# jtag-adapter-3-1.net
KiCad netlist of a schematic drawn in EAGLE
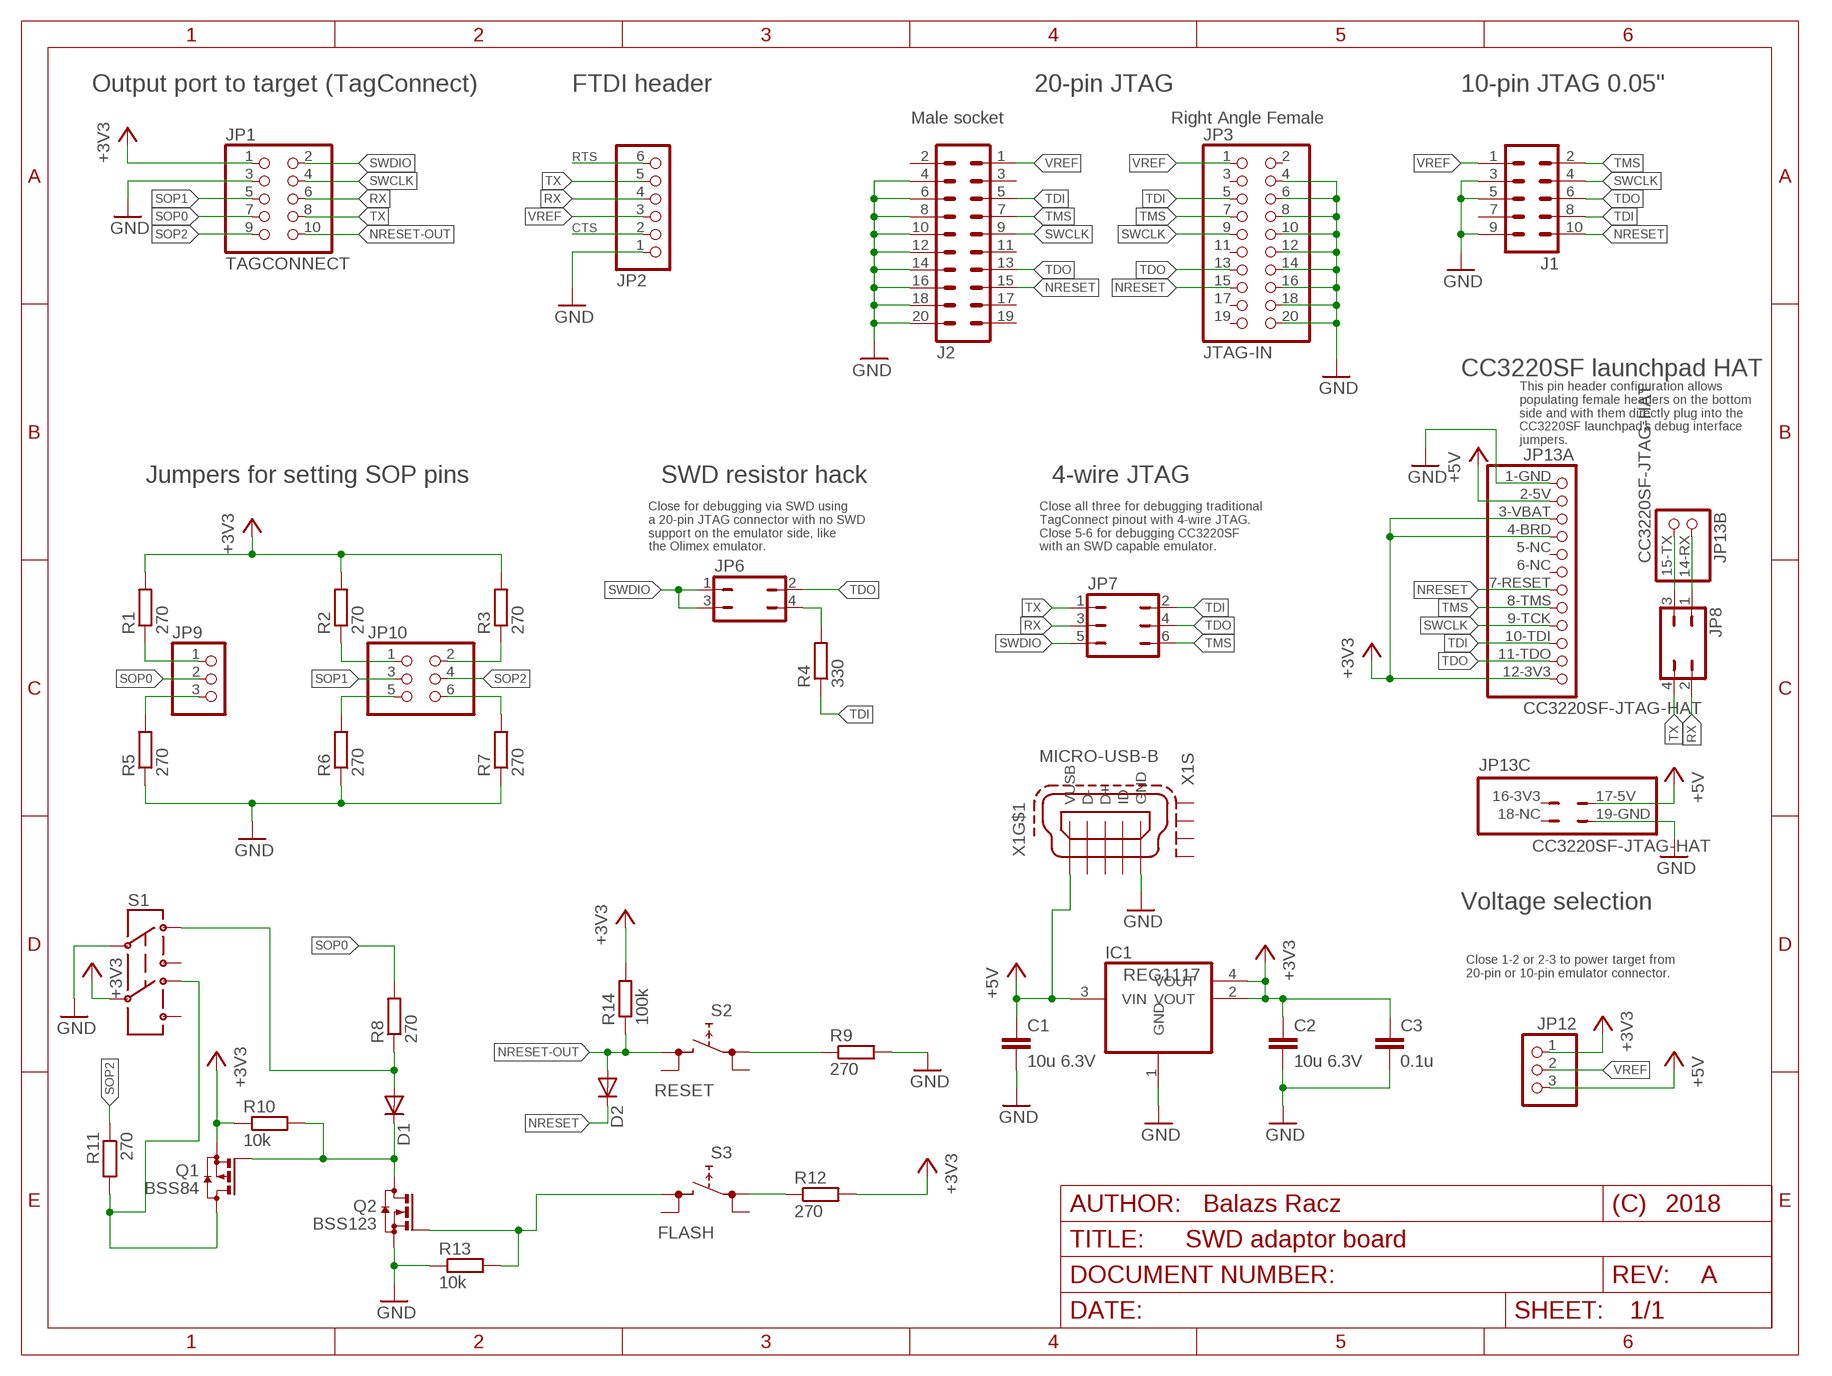
[diagram p0: schematic, sheet 1]

(export (version "E")
  (design (tool "Eeschema 10.0.6"))
  (components
    (comp (ref "C1")
      (value "10u 6.3V")
      (footprint "eagle-import:C0603K")
      (libsource (lib "eagle-import") (part "C-EUC0603K"))
    )
    (comp (ref "C2")
      (value "10u 6.3V")
      (footprint "eagle-import:C0603K")
      (libsource (lib "eagle-import") (part "C-EUC0603K"))
    )
    (comp (ref "C3")
      (value "0.1u")
      (footprint "eagle-import:C0603K")
      (libsource (lib "eagle-import") (part "C-EUC0603K"))
    )
    (comp (ref "D1")
      (value "DIODE-MINIMELF")
      (footprint "eagle-import:MINIMELF")
      (libsource (lib "eagle-import") (part "DIODE-MINIMELF"))
    )
    (comp (ref "D2")
      (value "DIODE-MINIMELF")
      (footprint "eagle-import:MINIMELF")
      (libsource (lib "eagle-import") (part "DIODE-MINIMELF"))
    )
    (comp (ref "IC1")
      (value "REG1117")
      (footprint "eagle-import:SOT223")
      (libsource (lib "eagle-import") (part "REG1117"))
    )
    (comp (ref "J1")
      (value "MA05-2_0.05X0.05")
      (footprint "eagle-import:MA05-2_0.05_X_0.05")
      (libsource (lib "eagle-import") (part "MA05-2_0.05X0.05"))
    )
    (comp (ref "J2")
      (value "MA10-2S")
      (footprint "eagle-import:MA10-2-SHROUDED")
      (libsource (lib "eagle-import") (part "MA10-2S"))
    )
    (comp (ref "JP1")
      (value "TAGCONNECT")
      (footprint "eagle-import:CON10M")
      (libsource (lib "eagle-import") (part "PINHD-2X5CN"))
    )
    (comp (ref "JP2")
      (value "PINHD-1X6")
      (footprint "eagle-import:1X06")
      (libsource (lib "eagle-import") (part "PINHD-1X6"))
    )
    (comp (ref "JP3")
      (value "JTAG-IN")
      (footprint "eagle-import:2X10")
      (libsource (lib "eagle-import") (part "PINHD-2X10"))
    )
    (comp (ref "JP6")
      (value "JP2Q")
      (footprint "eagle-import:JP2Q")
      (libsource (lib "eagle-import") (part "JP2Q"))
    )
    (comp (ref "JP7")
      (value "JP3Q")
      (footprint "eagle-import:JP3Q")
      (libsource (lib "eagle-import") (part "JP3Q"))
    )
    (comp (ref "JP8")
      (value "JP2Q")
      (footprint "eagle-import:JP2Q")
      (libsource (lib "eagle-import") (part "JP2Q"))
    )
    (comp (ref "JP9")
      (value "PINHD-1X3")
      (footprint "eagle-import:1X03")
      (libsource (lib "eagle-import") (part "PINHD-1X3"))
    )
    (comp (ref "JP10")
      (value "PINHD-2X3")
      (footprint "eagle-import:2X03")
      (libsource (lib "eagle-import") (part "PINHD-2X3"))
    )
    (comp (ref "JP12")
      (value "PINHD-1X3")
      (footprint "eagle-import:1X03")
      (libsource (lib "eagle-import") (part "PINHD-1X3"))
    )
    (comp (ref "JP13")
      (value "CC3220SF-JTAG-HAT")
      (footprint "eagle-import:JTAG-LAUNCHPAD-3220SF")
      (libsource (lib "eagle-import") (part "CC3220SF-JTAG-HAT"))
    )
    (comp (ref "Q1")
      (value "BSS84")
      (footprint "eagle-import:SOT23")
      (libsource (lib "eagle-import") (part "BSS84"))
    )
    (comp (ref "Q2")
      (value "BSS123")
      (footprint "eagle-import:SOT23")
      (libsource (lib "eagle-import") (part "BSS123"))
    )
    (comp (ref "R1")
      (value "270")
      (footprint "eagle-import:R0805")
      (libsource (lib "eagle-import") (part "R-EU_R0805"))
    )
    (comp (ref "R2")
      (value "270")
      (footprint "eagle-import:R0805")
      (libsource (lib "eagle-import") (part "R-EU_R0805"))
    )
    (comp (ref "R3")
      (value "270")
      (footprint "eagle-import:R0805")
      (libsource (lib "eagle-import") (part "R-EU_R0805"))
    )
    (comp (ref "R4")
      (value "330")
      (footprint "eagle-import:R0805")
      (libsource (lib "eagle-import") (part "R-EU_R0805"))
    )
    (comp (ref "R5")
      (value "270")
      (footprint "eagle-import:R0805")
      (libsource (lib "eagle-import") (part "R-EU_R0805"))
    )
    (comp (ref "R6")
      (value "270")
      (footprint "eagle-import:R0805")
      (libsource (lib "eagle-import") (part "R-EU_R0805"))
    )
    (comp (ref "R7")
      (value "270")
      (footprint "eagle-import:R0805")
      (libsource (lib "eagle-import") (part "R-EU_R0805"))
    )
    (comp (ref "R8")
      (value "270")
      (footprint "eagle-import:R0805")
      (libsource (lib "eagle-import") (part "R-EU_R0805"))
    )
    (comp (ref "R9")
      (value "270")
      (footprint "eagle-import:R0805")
      (libsource (lib "eagle-import") (part "R-EU_R0805"))
    )
    (comp (ref "R10")
      (value "10k")
      (footprint "eagle-import:R0805")
      (libsource (lib "eagle-import") (part "R-EU_R0805"))
    )
    (comp (ref "R11")
      (value "270")
      (footprint "eagle-import:R0805")
      (libsource (lib "eagle-import") (part "R-EU_R0805"))
    )
    (comp (ref "R12")
      (value "270")
      (footprint "eagle-import:R0805")
      (libsource (lib "eagle-import") (part "R-EU_R0805"))
    )
    (comp (ref "R13")
      (value "10k")
      (footprint "eagle-import:R0805")
      (libsource (lib "eagle-import") (part "R-EU_R0805"))
    )
    (comp (ref "R14")
      (value "100k")
      (footprint "eagle-import:R0805")
      (libsource (lib "eagle-import") (part "R-EU_R0805"))
    )
    (comp (ref "S1")
      (value "SWITCH-DPDTJS202011CQN")
      (footprint "eagle-import:DPDT-2.5X3.2MM")
      (libsource (lib "eagle-import") (part "SWITCH-DPDTJS202011CQN"))
    )
    (comp (ref "S2")
      (value "RESET")
      (footprint "eagle-import:TACTSW-6X6")
      (libsource (lib "eagle-import") (part "TACTSW-6X6S"))
    )
    (comp (ref "S3")
      (value "FLASH")
      (footprint "eagle-import:TACTSW-6X6")
      (libsource (lib "eagle-import") (part "TACTSW-6X6S"))
    )
    (comp (ref "X1")
      (value "MICRO-USB-B")
      (footprint "eagle-import:MICRO-B-PAC")
      (libsource (lib "eagle-import") (part "MICRO-USB-B"))
    )
  )
  (nets
    (net (code "1") (name "+3V3") (class "Default")
      (node (ref "C2") (pin "1") (pinfunction "1_1") (pintype "passive"))
      (node (ref "C3") (pin "1") (pinfunction "1_1") (pintype "passive"))
      (node (ref "IC1") (pin "2") (pinfunction "VOUT_2") (pintype "output"))
      (node (ref "IC1") (pin "4") (pinfunction "VOUT_4") (pintype "output"))
      (node (ref "JP1") (pin "1") (pinfunction "1_1") (pintype "passive"))
      (node (ref "JP12") (pin "1") (pinfunction "1_1") (pintype "passive"))
      (node (ref "JP13") (pin "12-3V3") (pinfunction "12_12-3V3") (pintype "passive"))
      (node (ref "JP13") (pin "3-VBAT") (pinfunction "3_3-VBAT") (pintype "passive"))
      (node (ref "JP13") (pin "4-BRD") (pinfunction "4_4-BRD") (pintype "passive"))
      (node (ref "Q1") (pin "2") (pinfunction "S_2") (pintype "passive"))
      (node (ref "R1") (pin "2") (pinfunction "2_2") (pintype "passive"))
      (node (ref "R10") (pin "1") (pinfunction "1_1") (pintype "passive"))
      (node (ref "R12") (pin "2") (pinfunction "2_2") (pintype "passive"))
      (node (ref "R14") (pin "2") (pinfunction "2_2") (pintype "passive"))
      (node (ref "R2") (pin "2") (pinfunction "2_2") (pintype "passive"))
      (node (ref "R3") (pin "2") (pinfunction "2_2") (pintype "passive"))
      (node (ref "S1") (pin "5") (pinfunction "2C_5") (pintype "bidirectional"))
    )
    (net (code "2") (name "+5V") (class "Default")
      (node (ref "C1") (pin "1") (pinfunction "1_1") (pintype "passive"))
      (node (ref "IC1") (pin "3") (pinfunction "VIN_3") (pintype "input"))
      (node (ref "JP12") (pin "3") (pinfunction "3_3") (pintype "passive"))
      (node (ref "JP13") (pin "17-5V") (pinfunction "2_17-5V") (pintype "passive"))
      (node (ref "JP13") (pin "2-5V") (pinfunction "2_2-5V") (pintype "passive"))
      (node (ref "X1") (pin "1") (pinfunction "VUSB_1") (pintype "passive"))
    )
    (net (code "3") (name "/CTS") (class "Default")
      (node (ref "JP2") (pin "2") (pinfunction "2_2") (pintype "passive"))
    )
    (net (code "4") (name "/RTS") (class "Default")
      (node (ref "JP2") (pin "6") (pinfunction "6_6") (pintype "passive"))
    )
    (net (code "5") (name "GND") (class "Default")
      (node (ref "C1") (pin "2") (pinfunction "2_2") (pintype "passive"))
      (node (ref "C2") (pin "2") (pinfunction "2_2") (pintype "passive"))
      (node (ref "C3") (pin "2") (pinfunction "2_2") (pintype "passive"))
      (node (ref "IC1") (pin "1") (pinfunction "GND_1") (pintype "power_in"))
      (node (ref "J1") (pin "3") (pinfunction "3_3") (pintype "passive"))
      (node (ref "J1") (pin "5") (pinfunction "5_5") (pintype "passive"))
      (node (ref "J1") (pin "9") (pinfunction "9_9") (pintype "passive"))
      (node (ref "J2") (pin "10") (pinfunction "10_10") (pintype "passive"))
      (node (ref "J2") (pin "12") (pinfunction "12_12") (pintype "passive"))
      (node (ref "J2") (pin "14") (pinfunction "14_14") (pintype "passive"))
      (node (ref "J2") (pin "16") (pinfunction "16_16") (pintype "passive"))
      (node (ref "J2") (pin "18") (pinfunction "18_18") (pintype "passive"))
      (node (ref "J2") (pin "20") (pinfunction "20_20") (pintype "passive"))
      (node (ref "J2") (pin "4") (pinfunction "4_4") (pintype "passive"))
      (node (ref "J2") (pin "6") (pinfunction "6_6") (pintype "passive"))
      (node (ref "J2") (pin "8") (pinfunction "8_8") (pintype "passive"))
      (node (ref "JP1") (pin "3") (pinfunction "3_3") (pintype "passive"))
      (node (ref "JP13") (pin "1-GND") (pinfunction "1_1-GND") (pintype "passive"))
      (node (ref "JP13") (pin "19-GND") (pinfunction "4_19-GND") (pintype "passive"))
      (node (ref "JP2") (pin "1") (pinfunction "1_1") (pintype "passive"))
      (node (ref "JP3") (pin "10") (pinfunction "10_10") (pintype "passive"))
      (node (ref "JP3") (pin "12") (pinfunction "12_12") (pintype "passive"))
      (node (ref "JP3") (pin "14") (pinfunction "14_14") (pintype "passive"))
      (node (ref "JP3") (pin "16") (pinfunction "16_16") (pintype "passive"))
      (node (ref "JP3") (pin "18") (pinfunction "18_18") (pintype "passive"))
      (node (ref "JP3") (pin "20") (pinfunction "20_20") (pintype "passive"))
      (node (ref "JP3") (pin "4") (pinfunction "4_4") (pintype "passive"))
      (node (ref "JP3") (pin "6") (pinfunction "6_6") (pintype "passive"))
      (node (ref "JP3") (pin "8") (pinfunction "8_8") (pintype "passive"))
      (node (ref "Q2") (pin "2") (pinfunction "S_2") (pintype "passive"))
      (node (ref "R13") (pin "1") (pinfunction "1_1") (pintype "passive"))
      (node (ref "R5") (pin "1") (pinfunction "1_1") (pintype "passive"))
      (node (ref "R6") (pin "1") (pinfunction "1_1") (pintype "passive"))
      (node (ref "R7") (pin "1") (pinfunction "1_1") (pintype "passive"))
      (node (ref "R9") (pin "2") (pinfunction "2_2") (pintype "passive"))
      (node (ref "S1") (pin "2") (pinfunction "1C_2") (pintype "bidirectional"))
      (node (ref "X1") (pin "5") (pinfunction "GND_5") (pintype "passive"))
    )
    (net (code "6") (name "NRESET") (class "Default")
      (node (ref "D2") (pin "C") (pinfunction "C_C") (pintype "passive"))
      (node (ref "J1") (pin "10") (pinfunction "10_10") (pintype "passive"))
      (node (ref "J2") (pin "15") (pinfunction "15_15") (pintype "passive"))
      (node (ref "JP13") (pin "7-RESET") (pinfunction "7_7-RESET") (pintype "passive"))
      (node (ref "JP3") (pin "15") (pinfunction "15_15") (pintype "passive"))
    )
    (net (code "7") (name "NRESET-OUT") (class "Default")
      (node (ref "D2") (pin "A") (pinfunction "A_A") (pintype "passive"))
      (node (ref "JP1") (pin "10") (pinfunction "10_10") (pintype "passive"))
      (node (ref "R14") (pin "1") (pinfunction "1_1") (pintype "passive"))
      (node (ref "S2") (pin "3") (pinfunction "2.1_3") (pintype "passive"))
    )
    (net (code "8") (name "Net-(JP6-Pad4)") (class "Default")
      (node (ref "JP6") (pin "4") (pinfunction "4_4") (pintype "passive"))
      (node (ref "R4") (pin "2") (pinfunction "2_2") (pintype "passive"))
    )
    (net (code "9") (name "Net-(JP9-Pad1)") (class "Default")
      (node (ref "JP9") (pin "1") (pinfunction "1_1") (pintype "passive"))
      (node (ref "R1") (pin "1") (pinfunction "1_1") (pintype "passive"))
    )
    (net (code "10") (name "Net-(JP9-Pad3)") (class "Default")
      (node (ref "JP9") (pin "3") (pinfunction "3_3") (pintype "passive"))
      (node (ref "R5") (pin "2") (pinfunction "2_2") (pintype "passive"))
    )
    (net (code "11") (name "Net-(JP10-Pad1)") (class "Default")
      (node (ref "JP10") (pin "1") (pinfunction "1_1") (pintype "passive"))
      (node (ref "R2") (pin "1") (pinfunction "1_1") (pintype "passive"))
    )
    (net (code "12") (name "Net-(JP10-Pad2)") (class "Default")
      (node (ref "JP10") (pin "2") (pinfunction "2_2") (pintype "passive"))
      (node (ref "R3") (pin "1") (pinfunction "1_1") (pintype "passive"))
    )
    (net (code "13") (name "Net-(JP10-Pad5)") (class "Default")
      (node (ref "JP10") (pin "5") (pinfunction "5_5") (pintype "passive"))
      (node (ref "R6") (pin "2") (pinfunction "2_2") (pintype "passive"))
    )
    (net (code "14") (name "Net-(JP10-Pad6)") (class "Default")
      (node (ref "JP10") (pin "6") (pinfunction "6_6") (pintype "passive"))
      (node (ref "R7") (pin "2") (pinfunction "2_2") (pintype "passive"))
    )
    (net (code "15") (name "Net-(JP13B-1)") (class "Default")
      (node (ref "JP13") (pin "14-RX") (pinfunction "1_14-RX") (pintype "passive"))
      (node (ref "JP8") (pin "1") (pinfunction "1_1") (pintype "passive"))
    )
    (net (code "16") (name "Net-(JP13B-2)") (class "Default")
      (node (ref "JP13") (pin "15-TX") (pinfunction "2_15-TX") (pintype "passive"))
      (node (ref "JP8") (pin "3") (pinfunction "3_3") (pintype "passive"))
    )
    (net (code "17") (name "Net-(Q1-D)") (class "Default")
      (node (ref "Q1") (pin "3") (pinfunction "D_3") (pintype "passive"))
      (node (ref "R11") (pin "2") (pinfunction "2_2") (pintype "passive"))
      (node (ref "S1") (pin "4") (pinfunction "2A_4") (pintype "bidirectional"))
    )
    (net (code "18") (name "Net-(Q1-G)") (class "Default")
      (node (ref "D1") (pin "C") (pinfunction "C_C") (pintype "passive"))
      (node (ref "Q1") (pin "1") (pinfunction "G_1") (pintype "passive"))
      (node (ref "Q2") (pin "3") (pinfunction "D_3") (pintype "passive"))
      (node (ref "R10") (pin "2") (pinfunction "2_2") (pintype "passive"))
    )
    (net (code "19") (name "Net-(Q2-G)") (class "Default")
      (node (ref "Q2") (pin "1") (pinfunction "G_1") (pintype "passive"))
      (node (ref "R13") (pin "2") (pinfunction "2_2") (pintype "passive"))
      (node (ref "S3") (pin "3") (pinfunction "2.1_3") (pintype "passive"))
    )
    (net (code "20") (name "Net-(S1-1A)") (class "Default")
      (node (ref "D1") (pin "A") (pinfunction "A_A") (pintype "passive"))
      (node (ref "R8") (pin "1") (pinfunction "1_1") (pintype "passive"))
      (node (ref "S1") (pin "1") (pinfunction "1A_1") (pintype "bidirectional"))
    )
    (net (code "21") (name "Net-(S2-1.1)") (class "Default")
      (node (ref "R9") (pin "1") (pinfunction "1_1") (pintype "passive"))
      (node (ref "S2") (pin "1") (pinfunction "1.1_1") (pintype "passive"))
    )
    (net (code "22") (name "Net-(S3-1.1)") (class "Default")
      (node (ref "R12") (pin "1") (pinfunction "1_1") (pintype "passive"))
      (node (ref "S3") (pin "1") (pinfunction "1.1_1") (pintype "passive"))
    )
    (net (code "23") (name "RX") (class "Default")
      (node (ref "JP1") (pin "6") (pinfunction "6_6") (pintype "passive"))
      (node (ref "JP2") (pin "4") (pinfunction "4_4") (pintype "passive"))
      (node (ref "JP7") (pin "3") (pinfunction "3_3") (pintype "passive"))
      (node (ref "JP8") (pin "2") (pinfunction "2_2") (pintype "passive"))
    )
    (net (code "24") (name "SOP0") (class "Default")
      (node (ref "JP1") (pin "7") (pinfunction "7_7") (pintype "passive"))
      (node (ref "JP9") (pin "2") (pinfunction "2_2") (pintype "passive"))
      (node (ref "R8") (pin "2") (pinfunction "2_2") (pintype "passive"))
    )
    (net (code "25") (name "SOP1") (class "Default")
      (node (ref "JP1") (pin "5") (pinfunction "5_5") (pintype "passive"))
      (node (ref "JP10") (pin "3") (pinfunction "3_3") (pintype "passive"))
    )
    (net (code "26") (name "SOP2") (class "Default")
      (node (ref "JP1") (pin "9") (pinfunction "9_9") (pintype "passive"))
      (node (ref "JP10") (pin "4") (pinfunction "4_4") (pintype "passive"))
      (node (ref "R11") (pin "1") (pinfunction "1_1") (pintype "passive"))
    )
    (net (code "27") (name "SWCLK") (class "Default")
      (node (ref "J1") (pin "4") (pinfunction "4_4") (pintype "passive"))
      (node (ref "J2") (pin "9") (pinfunction "9_9") (pintype "passive"))
      (node (ref "JP1") (pin "4") (pinfunction "4_4") (pintype "passive"))
      (node (ref "JP13") (pin "9-TCK") (pinfunction "9_9-TCK") (pintype "passive"))
      (node (ref "JP3") (pin "9") (pinfunction "9_9") (pintype "passive"))
    )
    (net (code "28") (name "SWDIO") (class "Default")
      (node (ref "JP1") (pin "2") (pinfunction "2_2") (pintype "passive"))
      (node (ref "JP6") (pin "1") (pinfunction "1_1") (pintype "passive"))
      (node (ref "JP6") (pin "3") (pinfunction "3_3") (pintype "passive"))
      (node (ref "JP7") (pin "5") (pinfunction "5_5") (pintype "passive"))
    )
    (net (code "29") (name "TDI") (class "Default")
      (node (ref "J1") (pin "8") (pinfunction "8_8") (pintype "passive"))
      (node (ref "J2") (pin "5") (pinfunction "5_5") (pintype "passive"))
      (node (ref "JP13") (pin "10-TDI") (pinfunction "10_10-TDI") (pintype "passive"))
      (node (ref "JP3") (pin "5") (pinfunction "5_5") (pintype "passive"))
      (node (ref "JP7") (pin "2") (pinfunction "2_2") (pintype "passive"))
      (node (ref "R4") (pin "1") (pinfunction "1_1") (pintype "passive"))
    )
    (net (code "30") (name "TDO") (class "Default")
      (node (ref "J1") (pin "6") (pinfunction "6_6") (pintype "passive"))
      (node (ref "J2") (pin "13") (pinfunction "13_13") (pintype "passive"))
      (node (ref "JP13") (pin "11-TDO") (pinfunction "11_11-TDO") (pintype "passive"))
      (node (ref "JP3") (pin "13") (pinfunction "13_13") (pintype "passive"))
      (node (ref "JP6") (pin "2") (pinfunction "2_2") (pintype "passive"))
      (node (ref "JP7") (pin "4") (pinfunction "4_4") (pintype "passive"))
    )
    (net (code "31") (name "TMS") (class "Default")
      (node (ref "J1") (pin "2") (pinfunction "2_2") (pintype "passive"))
      (node (ref "J2") (pin "7") (pinfunction "7_7") (pintype "passive"))
      (node (ref "JP13") (pin "8-TMS") (pinfunction "8_8-TMS") (pintype "passive"))
      (node (ref "JP3") (pin "7") (pinfunction "7_7") (pintype "passive"))
      (node (ref "JP7") (pin "6") (pinfunction "6_6") (pintype "passive"))
    )
    (net (code "32") (name "TX") (class "Default")
      (node (ref "JP1") (pin "8") (pinfunction "8_8") (pintype "passive"))
      (node (ref "JP2") (pin "5") (pinfunction "5_5") (pintype "passive"))
      (node (ref "JP7") (pin "1") (pinfunction "1_1") (pintype "passive"))
      (node (ref "JP8") (pin "4") (pinfunction "4_4") (pintype "passive"))
    )
    (net (code "33") (name "VREF") (class "Default")
      (node (ref "J1") (pin "1") (pinfunction "1_1") (pintype "passive"))
      (node (ref "J2") (pin "1") (pinfunction "1_1") (pintype "passive"))
      (node (ref "JP12") (pin "2") (pinfunction "2_2") (pintype "passive"))
      (node (ref "JP2") (pin "3") (pinfunction "3_3") (pintype "passive"))
      (node (ref "JP3") (pin "1") (pinfunction "1_1") (pintype "passive"))
    )
    (net (code "34") (name "unconnected-(J1-Pad7)") (class "Default")
      (node (ref "J1") (pin "7") (pinfunction "7_7") (pintype "passive"))
    )
    (net (code "35") (name "unconnected-(J2-Pad2)") (class "Default")
      (node (ref "J2") (pin "2") (pinfunction "2_2") (pintype "passive"))
    )
    (net (code "36") (name "unconnected-(J2-Pad3)") (class "Default")
      (node (ref "J2") (pin "3") (pinfunction "3_3") (pintype "passive"))
    )
    (net (code "37") (name "unconnected-(J2-Pad11)") (class "Default")
      (node (ref "J2") (pin "11") (pinfunction "11_11") (pintype "passive"))
    )
    (net (code "38") (name "unconnected-(J2-Pad17)") (class "Default")
      (node (ref "J2") (pin "17") (pinfunction "17_17") (pintype "passive"))
    )
    (net (code "39") (name "unconnected-(J2-Pad19)") (class "Default")
      (node (ref "J2") (pin "19") (pinfunction "19_19") (pintype "passive"))
    )
    (net (code "40") (name "unconnected-(JP3-Pad2)") (class "Default")
      (node (ref "JP3") (pin "2") (pinfunction "2_2") (pintype "passive"))
    )
    (net (code "41") (name "unconnected-(JP3-Pad3)") (class "Default")
      (node (ref "JP3") (pin "3") (pinfunction "3_3") (pintype "passive"))
    )
    (net (code "42") (name "unconnected-(JP3-Pad11)") (class "Default")
      (node (ref "JP3") (pin "11") (pinfunction "11_11") (pintype "passive"))
    )
    (net (code "43") (name "unconnected-(JP3-Pad17)") (class "Default")
      (node (ref "JP3") (pin "17") (pinfunction "17_17") (pintype "passive"))
    )
    (net (code "44") (name "unconnected-(JP3-Pad19)") (class "Default")
      (node (ref "JP3") (pin "19") (pinfunction "19_19") (pintype "passive"))
    )
    (net (code "45") (name "unconnected-(JP13A-5-Pad5-NC)") (class "Default")
      (node (ref "JP13") (pin "5-NC") (pinfunction "5_5-NC") (pintype "passive"))
    )
    (net (code "46") (name "unconnected-(JP13A-6-Pad6-NC)") (class "Default")
      (node (ref "JP13") (pin "6-NC") (pinfunction "6_6-NC") (pintype "passive"))
    )
    (net (code "47") (name "unconnected-(JP13C-1-Pad16-3V3)") (class "Default")
      (node (ref "JP13") (pin "16-3V3") (pinfunction "1_16-3V3") (pintype "passive"))
    )
    (net (code "48") (name "unconnected-(JP13C-3-Pad18-NC)") (class "Default")
      (node (ref "JP13") (pin "18-NC") (pinfunction "3_18-NC") (pintype "passive"))
    )
    (net (code "49") (name "unconnected-(S1-1B-Pad3)") (class "Default")
      (node (ref "S1") (pin "3") (pinfunction "1B_3") (pintype "bidirectional"))
    )
    (net (code "50") (name "unconnected-(S1-2B-Pad6)") (class "Default")
      (node (ref "S1") (pin "6") (pinfunction "2B_6") (pintype "bidirectional"))
    )
    (net (code "51") (name "unconnected-(S2-1.2-Pad2)") (class "Default")
      (node (ref "S2") (pin "2") (pinfunction "1.2_2") (pintype "passive"))
    )
    (net (code "52") (name "unconnected-(S2-2.2-Pad4)") (class "Default")
      (node (ref "S2") (pin "4") (pinfunction "2.2_4") (pintype "passive"))
    )
    (net (code "53") (name "unconnected-(S3-1.2-Pad2)") (class "Default")
      (node (ref "S3") (pin "2") (pinfunction "1.2_2") (pintype "passive"))
    )
    (net (code "54") (name "unconnected-(S3-2.2-Pad4)") (class "Default")
      (node (ref "S3") (pin "4") (pinfunction "2.2_4") (pintype "passive"))
    )
    (net (code "55") (name "unconnected-(X1A-D+-Pad3)") (class "Default")
      (node (ref "X1") (pin "3") (pinfunction "D+_3") (pintype "passive"))
    )
    (net (code "56") (name "unconnected-(X1A-D--Pad2)") (class "Default")
      (node (ref "X1") (pin "2") (pinfunction "D-_2") (pintype "passive"))
    )
    (net (code "57") (name "unconnected-(X1A-ID-Pad4)") (class "Default")
      (node (ref "X1") (pin "4") (pinfunction "ID_4") (pintype "passive"))
    )
    (net (code "58") (name "unconnected-(X1B-S1-PadM1)") (class "Default")
      (node (ref "X1") (pin "M1") (pinfunction "S1_M1") (pintype "passive"))
    )
    (net (code "59") (name "unconnected-(X1B-S2-PadM2)") (class "Default")
      (node (ref "X1") (pin "M2") (pinfunction "S2_M2") (pintype "passive"))
    )
    (net (code "60") (name "unconnected-(X1B-S3-PadM3)") (class "Default")
      (node (ref "X1") (pin "M3") (pinfunction "S3_M3") (pintype "passive"))
    )
    (net (code "61") (name "unconnected-(X1B-S4-PadM4)") (class "Default")
      (node (ref "X1") (pin "M4") (pinfunction "S4_M4") (pintype "passive"))
    )
  )
)
